# hovercraft_brian-pc_s_conflicted_copy_20.net
KiCad netlist of a schematic drawn in EAGLE
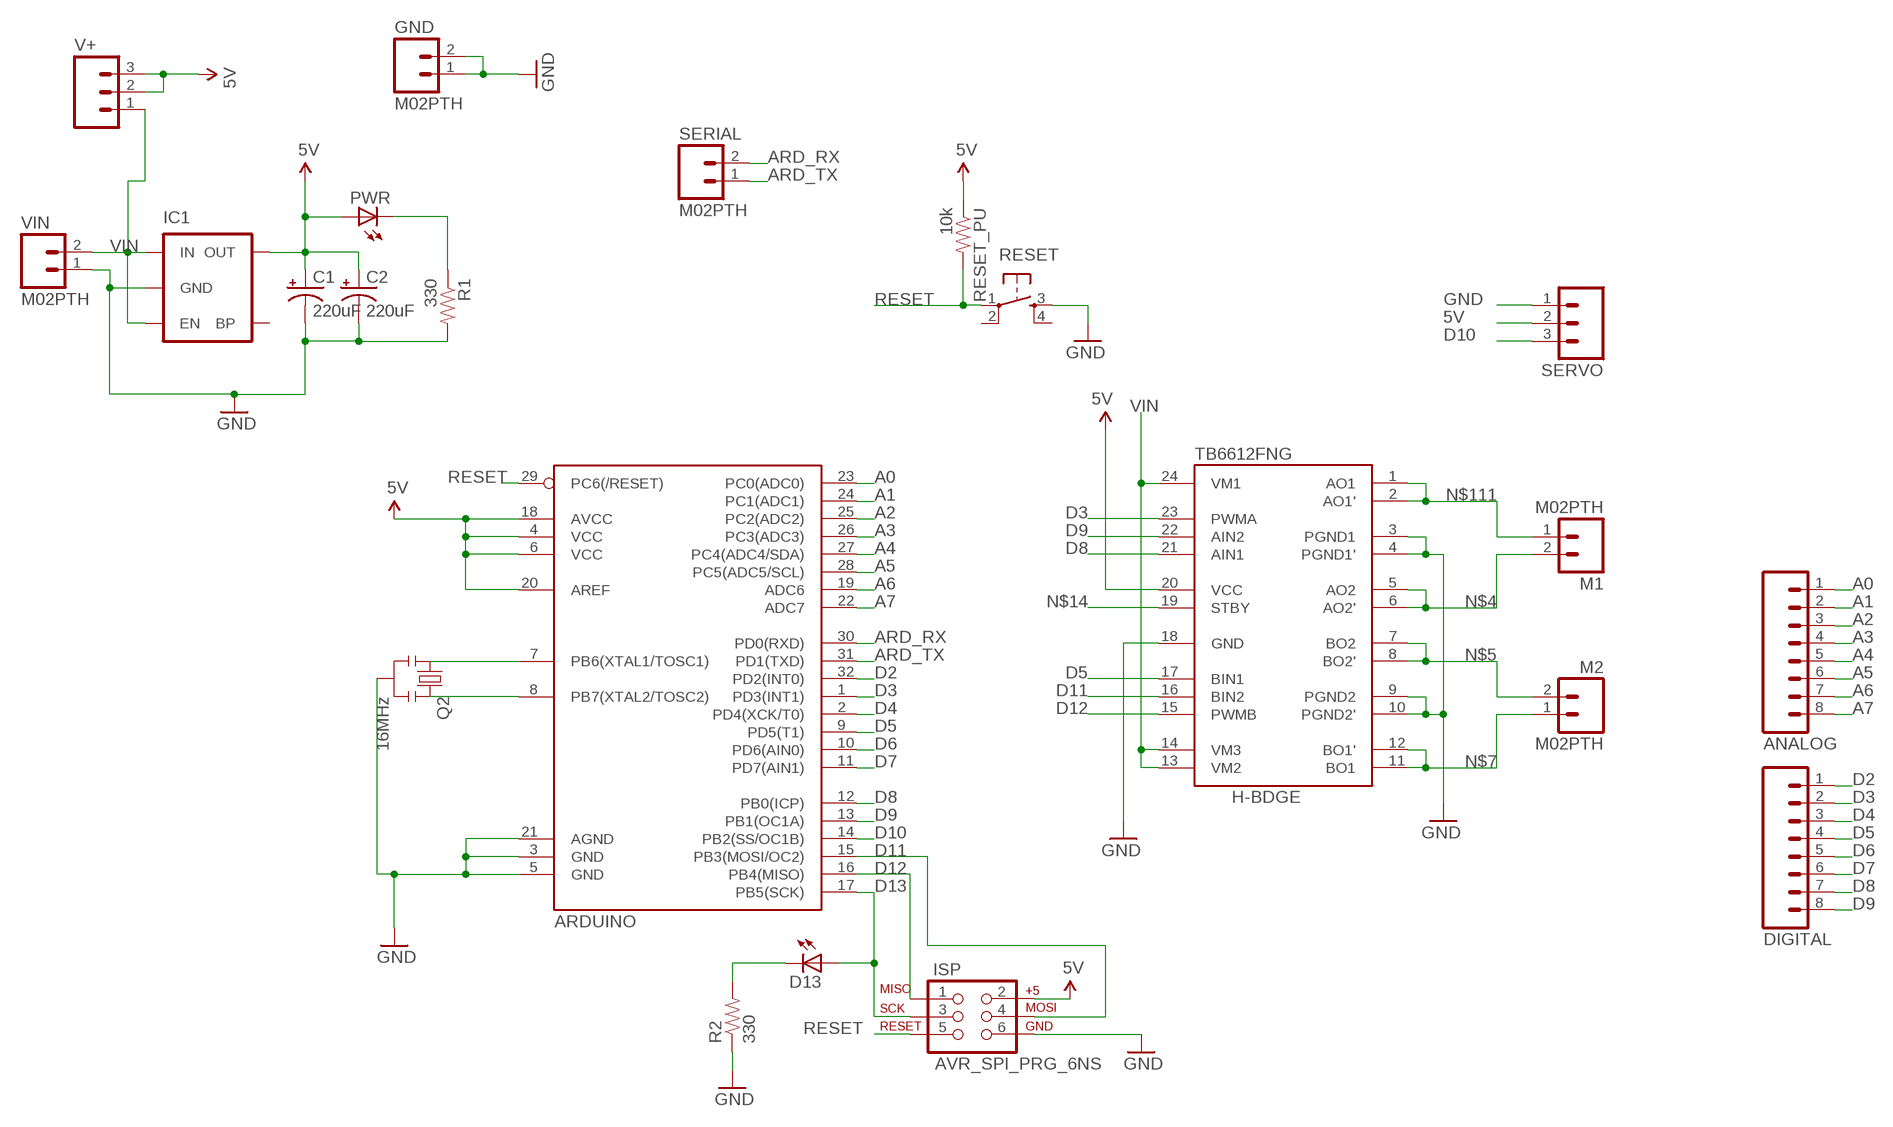
[diagram p0: schematic, sheet 1]

(export (version "E")
  (design (tool "Eeschema 10.0.6"))
  (components
    (comp (ref "ANALOG")
      (value "M08LOCK")
      (footprint "eagle-import:1X08_LOCK")
      (libsource (lib "eagle-import") (part "M08LOCK"))
    )
    (comp (ref "ARDUINO")
      (value "ATMEGA328_SMT")
      (footprint "eagle-import:TQFP32-08")
      (libsource (lib "eagle-import") (part "ATMEGA328_SMT"))
    )
    (comp (ref "C1")
      (value "220uF")
      (footprint "eagle-import:CPOL-RADIAL-100UF-25V")
      (libsource (lib "eagle-import") (part "CAP_POLPTH1"))
    )
    (comp (ref "C2")
      (value "220uF")
      (footprint "eagle-import:CPOL-RADIAL-100UF-25V")
      (libsource (lib "eagle-import") (part "CAP_POLPTH1"))
    )
    (comp (ref "D13")
      (value "LEDCHIPLED_0805")
      (footprint "eagle-import:CHIPLED_0805")
      (libsource (lib "eagle-import") (part "LEDCHIPLED_0805"))
    )
    (comp (ref "DIGITAL")
      (value "M08LOCK")
      (footprint "eagle-import:1X08_LOCK")
      (libsource (lib "eagle-import") (part "M08LOCK"))
    )
    (comp (ref "GND")
      (value "M02PTH")
      (footprint "eagle-import:1X02")
      (libsource (lib "eagle-import") (part "M02PTH"))
    )
    (comp (ref "H-BDGE")
      (value "TB6612FNG")
      (footprint "eagle-import:SSOP24")
      (libsource (lib "eagle-import") (part "TB6612FNG"))
    )
    (comp (ref "IC1")
      (value "MIC52055V")
      (footprint "eagle-import:SOT23-5")
      (libsource (lib "eagle-import") (part "MIC52055V"))
    )
    (comp (ref "ISP")
      (value "AVR_SPI_PRG_6NS")
      (footprint "eagle-import:2X3-NS")
      (libsource (lib "eagle-import") (part "AVR_SPI_PRG_6NS"))
    )
    (comp (ref "M1")
      (value "M02PTH")
      (footprint "eagle-import:1X02")
      (libsource (lib "eagle-import") (part "M02PTH"))
    )
    (comp (ref "M2")
      (value "M02PTH")
      (footprint "eagle-import:1X02")
      (libsource (lib "eagle-import") (part "M02PTH"))
    )
    (comp (ref "PWR")
      (value "LEDCHIPLED_0805")
      (footprint "eagle-import:CHIPLED_0805")
      (libsource (lib "eagle-import") (part "LEDCHIPLED_0805"))
    )
    (comp (ref "Q2")
      (value "16MHz")
      (footprint "eagle-import:RESONATOR-SMD")
      (libsource (lib "eagle-import") (part "RESONATOR16MHZ"))
    )
    (comp (ref "R1")
      (value "330")
      (footprint "eagle-import:0805")
      (libsource (lib "eagle-import") (part "RESISTOR0805-RES"))
    )
    (comp (ref "R2")
      (value "330")
      (footprint "eagle-import:0805")
      (libsource (lib "eagle-import") (part "RESISTOR0805-RES"))
    )
    (comp (ref "RESET")
      (value "TAC_SWITCHSMD")
      (footprint "eagle-import:TACTILE_SWITCH_SMD")
      (libsource (lib "eagle-import") (part "TAC_SWITCHSMD"))
    )
    (comp (ref "RESET_PU")
      (value "10k")
      (footprint "eagle-import:0805")
      (libsource (lib "eagle-import") (part "RESISTOR0805-RES"))
    )
    (comp (ref "SERIAL")
      (value "M02PTH")
      (footprint "eagle-import:1X02")
      (libsource (lib "eagle-import") (part "M02PTH"))
    )
    (comp (ref "SERVO")
      (value "M03PTH")
      (footprint "eagle-import:1X03")
      (libsource (lib "eagle-import") (part "M03PTH"))
    )
    (comp (ref "V+")
      (value "M03PTH")
      (footprint "eagle-import:1X03")
      (libsource (lib "eagle-import") (part "M03PTH"))
    )
    (comp (ref "VIN")
      (value "M02PTH")
      (footprint "eagle-import:1X02")
      (libsource (lib "eagle-import") (part "M02PTH"))
    )
  )
  (nets
    (net (code "1") (name "/A0") (class "Default")
      (node (ref "ANALOG") (pin "1") (pinfunction "1_1") (pintype "passive"))
      (node (ref "ARDUINO") (pin "23") (pinfunction "PC0(ADC0)_23") (pintype "bidirectional"))
    )
    (net (code "2") (name "/A1") (class "Default")
      (node (ref "ANALOG") (pin "2") (pinfunction "2_2") (pintype "passive"))
      (node (ref "ARDUINO") (pin "24") (pinfunction "PC1(ADC1)_24") (pintype "bidirectional"))
    )
    (net (code "3") (name "/A2") (class "Default")
      (node (ref "ANALOG") (pin "3") (pinfunction "3_3") (pintype "passive"))
      (node (ref "ARDUINO") (pin "25") (pinfunction "PC2(ADC2)_25") (pintype "bidirectional"))
    )
    (net (code "4") (name "/A3") (class "Default")
      (node (ref "ANALOG") (pin "4") (pinfunction "4_4") (pintype "passive"))
      (node (ref "ARDUINO") (pin "26") (pinfunction "PC3(ADC3)_26") (pintype "bidirectional"))
    )
    (net (code "5") (name "/A4") (class "Default")
      (node (ref "ANALOG") (pin "5") (pinfunction "5_5") (pintype "passive"))
      (node (ref "ARDUINO") (pin "27") (pinfunction "PC4(ADC4/SDA)_27") (pintype "bidirectional"))
    )
    (net (code "6") (name "/A5") (class "Default")
      (node (ref "ANALOG") (pin "6") (pinfunction "6_6") (pintype "passive"))
      (node (ref "ARDUINO") (pin "28") (pinfunction "PC5(ADC5/SCL)_28") (pintype "bidirectional"))
    )
    (net (code "7") (name "/A6") (class "Default")
      (node (ref "ANALOG") (pin "7") (pinfunction "7_7") (pintype "passive"))
      (node (ref "ARDUINO") (pin "19") (pinfunction "ADC6_19") (pintype "bidirectional"))
    )
    (net (code "8") (name "/A7") (class "Default")
      (node (ref "ANALOG") (pin "8") (pinfunction "8_8") (pintype "passive"))
      (node (ref "ARDUINO") (pin "22") (pinfunction "ADC7_22") (pintype "bidirectional"))
    )
    (net (code "9") (name "/ARD_RX") (class "Default")
      (node (ref "ARDUINO") (pin "30") (pinfunction "PD0(RXD)_30") (pintype "bidirectional"))
      (node (ref "SERIAL") (pin "2") (pinfunction "2_2") (pintype "passive"))
    )
    (net (code "10") (name "/ARD_TX") (class "Default")
      (node (ref "ARDUINO") (pin "31") (pinfunction "PD1(TXD)_31") (pintype "bidirectional"))
      (node (ref "SERIAL") (pin "1") (pinfunction "1_1") (pintype "passive"))
    )
    (net (code "11") (name "/D2") (class "Default")
      (node (ref "ARDUINO") (pin "32") (pinfunction "PD2(INT0)_32") (pintype "bidirectional"))
      (node (ref "DIGITAL") (pin "1") (pinfunction "1_1") (pintype "passive"))
    )
    (net (code "12") (name "/D3") (class "Default")
      (node (ref "ARDUINO") (pin "1") (pinfunction "PD3(INT1)_1") (pintype "bidirectional"))
      (node (ref "DIGITAL") (pin "2") (pinfunction "2_2") (pintype "passive"))
      (node (ref "H-BDGE") (pin "23") (pinfunction "PWMA_23") (pintype "input"))
    )
    (net (code "13") (name "/D4") (class "Default")
      (node (ref "ARDUINO") (pin "2") (pinfunction "PD4(XCK/T0)_2") (pintype "bidirectional"))
      (node (ref "DIGITAL") (pin "3") (pinfunction "3_3") (pintype "passive"))
    )
    (net (code "14") (name "/D5") (class "Default")
      (node (ref "ARDUINO") (pin "9") (pinfunction "PD5(T1)_9") (pintype "bidirectional"))
      (node (ref "DIGITAL") (pin "4") (pinfunction "4_4") (pintype "passive"))
      (node (ref "H-BDGE") (pin "17") (pinfunction "BIN1_17") (pintype "input"))
    )
    (net (code "15") (name "/D6") (class "Default")
      (node (ref "ARDUINO") (pin "10") (pinfunction "PD6(AIN0)_10") (pintype "bidirectional"))
      (node (ref "DIGITAL") (pin "5") (pinfunction "5_5") (pintype "passive"))
    )
    (net (code "16") (name "/D7") (class "Default")
      (node (ref "ARDUINO") (pin "11") (pinfunction "PD7(AIN1)_11") (pintype "bidirectional"))
      (node (ref "DIGITAL") (pin "6") (pinfunction "6_6") (pintype "passive"))
    )
    (net (code "17") (name "/D8") (class "Default")
      (node (ref "ARDUINO") (pin "12") (pinfunction "PB0(ICP)_12") (pintype "bidirectional"))
      (node (ref "DIGITAL") (pin "7") (pinfunction "7_7") (pintype "passive"))
      (node (ref "H-BDGE") (pin "21") (pinfunction "AIN1_21") (pintype "input"))
    )
    (net (code "18") (name "/D9") (class "Default")
      (node (ref "ARDUINO") (pin "13") (pinfunction "PB1(OC1A)_13") (pintype "bidirectional"))
      (node (ref "DIGITAL") (pin "8") (pinfunction "8_8") (pintype "passive"))
      (node (ref "H-BDGE") (pin "22") (pinfunction "AIN2_22") (pintype "input"))
    )
    (net (code "19") (name "/D10") (class "Default")
      (node (ref "ARDUINO") (pin "14") (pinfunction "PB2(SS/OC1B)_14") (pintype "bidirectional"))
      (node (ref "SERVO") (pin "3") (pinfunction "3_3") (pintype "passive"))
    )
    (net (code "20") (name "/D11") (class "Default")
      (node (ref "ARDUINO") (pin "15") (pinfunction "PB3(MOSI/OC2)_15") (pintype "bidirectional"))
      (node (ref "H-BDGE") (pin "16") (pinfunction "BIN2_16") (pintype "input"))
      (node (ref "ISP") (pin "4") (pinfunction "4_4") (pintype "passive"))
    )
    (net (code "21") (name "/D12") (class "Default")
      (node (ref "ARDUINO") (pin "16") (pinfunction "PB4(MISO)_16") (pintype "bidirectional"))
      (node (ref "H-BDGE") (pin "15") (pinfunction "PWMB_15") (pintype "input"))
      (node (ref "ISP") (pin "1") (pinfunction "1_1") (pintype "passive"))
    )
    (net (code "22") (name "/D13") (class "Default")
      (node (ref "ARDUINO") (pin "17") (pinfunction "PB5(SCK)_17") (pintype "bidirectional"))
      (node (ref "D13") (pin "A") (pinfunction "A_A") (pintype "passive"))
      (node (ref "ISP") (pin "3") (pinfunction "3_3") (pintype "passive"))
    )
    (net (code "23") (name "/N$4") (class "Default")
      (node (ref "H-BDGE") (pin "5") (pinfunction "AO2_5") (pintype "output"))
      (node (ref "H-BDGE") (pin "6") (pinfunction "AO2'_6") (pintype "output"))
      (node (ref "M1") (pin "2") (pinfunction "2_2") (pintype "passive"))
    )
    (net (code "24") (name "/N$5") (class "Default")
      (node (ref "H-BDGE") (pin "7") (pinfunction "BO2_7") (pintype "output"))
      (node (ref "H-BDGE") (pin "8") (pinfunction "BO2'_8") (pintype "output"))
      (node (ref "M2") (pin "2") (pinfunction "2_2") (pintype "passive"))
    )
    (net (code "25") (name "/N$7") (class "Default")
      (node (ref "H-BDGE") (pin "11") (pinfunction "BO1_11") (pintype "output"))
      (node (ref "H-BDGE") (pin "12") (pinfunction "BO1'_12") (pintype "output"))
      (node (ref "M2") (pin "1") (pinfunction "1_1") (pintype "passive"))
    )
    (net (code "26") (name "/N$14") (class "Default")
      (node (ref "H-BDGE") (pin "19") (pinfunction "STBY_19") (pintype "input"))
    )
    (net (code "27") (name "/N$111") (class "Default")
      (node (ref "H-BDGE") (pin "1") (pinfunction "AO1_1") (pintype "output"))
      (node (ref "H-BDGE") (pin "2") (pinfunction "AO1'_2") (pintype "output"))
      (node (ref "M1") (pin "1") (pinfunction "1_1") (pintype "passive"))
    )
    (net (code "28") (name "/RESET") (class "Default")
      (node (ref "ARDUINO") (pin "29") (pinfunction "PC6(/RESET)_29") (pintype "bidirectional"))
      (node (ref "ISP") (pin "5") (pinfunction "5_5") (pintype "passive"))
      (node (ref "RESET") (pin "1") (pinfunction "1_1") (pintype "passive"))
      (node (ref "RESET_PU") (pin "2") (pinfunction "2_2") (pintype "passive"))
    )
    (net (code "29") (name "/VIN") (class "Default")
      (node (ref "H-BDGE") (pin "13") (pinfunction "VM2_13") (pintype "power_in"))
      (node (ref "H-BDGE") (pin "14") (pinfunction "VM3_14") (pintype "power_in"))
      (node (ref "H-BDGE") (pin "24") (pinfunction "VM1_24") (pintype "power_in"))
      (node (ref "IC1") (pin "1") (pinfunction "IN_1") (pintype "input"))
      (node (ref "IC1") (pin "3") (pinfunction "EN_3") (pintype "input"))
      (node (ref "V+") (pin "1") (pinfunction "1_1") (pintype "passive"))
      (node (ref "VIN") (pin "2") (pinfunction "2_2") (pintype "passive"))
    )
    (net (code "30") (name "5V") (class "Default")
      (node (ref "ARDUINO") (pin "18") (pinfunction "AVCC_18") (pintype "bidirectional"))
      (node (ref "ARDUINO") (pin "20") (pinfunction "AREF_20") (pintype "bidirectional"))
      (node (ref "ARDUINO") (pin "4") (pinfunction "VCC_4") (pintype "bidirectional"))
      (node (ref "ARDUINO") (pin "6") (pinfunction "VCC_6") (pintype "bidirectional"))
      (node (ref "C1") (pin "1") (pinfunction "+_1") (pintype "passive"))
      (node (ref "C2") (pin "1") (pinfunction "+_1") (pintype "passive"))
      (node (ref "H-BDGE") (pin "20") (pinfunction "VCC_20") (pintype "power_in"))
      (node (ref "IC1") (pin "5") (pinfunction "OUT_5") (pintype "passive"))
      (node (ref "ISP") (pin "2") (pinfunction "2_2") (pintype "passive"))
      (node (ref "PWR") (pin "A") (pinfunction "A_A") (pintype "passive"))
      (node (ref "RESET_PU") (pin "1") (pinfunction "1_1") (pintype "passive"))
      (node (ref "SERVO") (pin "2") (pinfunction "2_2") (pintype "passive"))
      (node (ref "V+") (pin "2") (pinfunction "2_2") (pintype "passive"))
      (node (ref "V+") (pin "3") (pinfunction "3_3") (pintype "passive"))
    )
    (net (code "31") (name "GND") (class "Default")
      (node (ref "ARDUINO") (pin "21") (pinfunction "AGND_21") (pintype "bidirectional"))
      (node (ref "ARDUINO") (pin "3") (pinfunction "GND_3") (pintype "bidirectional"))
      (node (ref "ARDUINO") (pin "5") (pinfunction "GND_5") (pintype "bidirectional"))
      (node (ref "C1") (pin "2") (pinfunction "-_2") (pintype "passive"))
      (node (ref "C2") (pin "2") (pinfunction "-_2") (pintype "passive"))
      (node (ref "GND") (pin "1") (pinfunction "1_1") (pintype "passive"))
      (node (ref "GND") (pin "2") (pinfunction "2_2") (pintype "passive"))
      (node (ref "H-BDGE") (pin "10") (pinfunction "PGND2'_10") (pintype "power_in"))
      (node (ref "H-BDGE") (pin "18") (pinfunction "GND_18") (pintype "power_in"))
      (node (ref "H-BDGE") (pin "3") (pinfunction "PGND1_3") (pintype "power_in"))
      (node (ref "H-BDGE") (pin "4") (pinfunction "PGND1'_4") (pintype "power_in"))
      (node (ref "H-BDGE") (pin "9") (pinfunction "PGND2_9") (pintype "power_in"))
      (node (ref "IC1") (pin "2") (pinfunction "GND_2") (pintype "input"))
      (node (ref "ISP") (pin "6") (pinfunction "6_6") (pintype "passive"))
      (node (ref "Q2") (pin "2") (pinfunction "2_2") (pintype "passive"))
      (node (ref "R1") (pin "2") (pinfunction "2_2") (pintype "passive"))
      (node (ref "R2") (pin "1") (pinfunction "1_1") (pintype "passive"))
      (node (ref "RESET") (pin "3") (pinfunction "3_3") (pintype "passive"))
      (node (ref "SERVO") (pin "1") (pinfunction "1_1") (pintype "passive"))
      (node (ref "VIN") (pin "1") (pinfunction "1_1") (pintype "passive"))
    )
    (net (code "32") (name "Net-(ARDUINO-PB6(XTAL1{slash}TOSC1))") (class "Default")
      (node (ref "ARDUINO") (pin "7") (pinfunction "PB6(XTAL1/TOSC1)_7") (pintype "bidirectional"))
      (node (ref "Q2") (pin "1") (pinfunction "1_1") (pintype "passive"))
    )
    (net (code "33") (name "Net-(ARDUINO-PB7(XTAL2{slash}TOSC2))") (class "Default")
      (node (ref "ARDUINO") (pin "8") (pinfunction "PB7(XTAL2/TOSC2)_8") (pintype "bidirectional"))
      (node (ref "Q2") (pin "3") (pinfunction "3_3") (pintype "passive"))
    )
    (net (code "34") (name "Net-(D13-PadC)") (class "Default")
      (node (ref "D13") (pin "C") (pinfunction "C_C") (pintype "passive"))
      (node (ref "R2") (pin "2") (pinfunction "2_2") (pintype "passive"))
    )
    (net (code "35") (name "Net-(PWR-PadC)") (class "Default")
      (node (ref "PWR") (pin "C") (pinfunction "C_C") (pintype "passive"))
      (node (ref "R1") (pin "1") (pinfunction "1_1") (pintype "passive"))
    )
    (net (code "36") (name "unconnected-(IC1-BP-Pad4)") (class "Default")
      (node (ref "IC1") (pin "4") (pinfunction "BP_4") (pintype "input"))
    )
    (net (code "37") (name "unconnected-(RESET-Pad2)") (class "Default")
      (node (ref "RESET") (pin "2") (pinfunction "2_2") (pintype "passive"))
    )
    (net (code "38") (name "unconnected-(RESET-Pad4)") (class "Default")
      (node (ref "RESET") (pin "4") (pinfunction "4_4") (pintype "passive"))
    )
  )
)
